# IDC_BNC_Adapter.net
KiCad netlist of a schematic drawn in Altium Designer
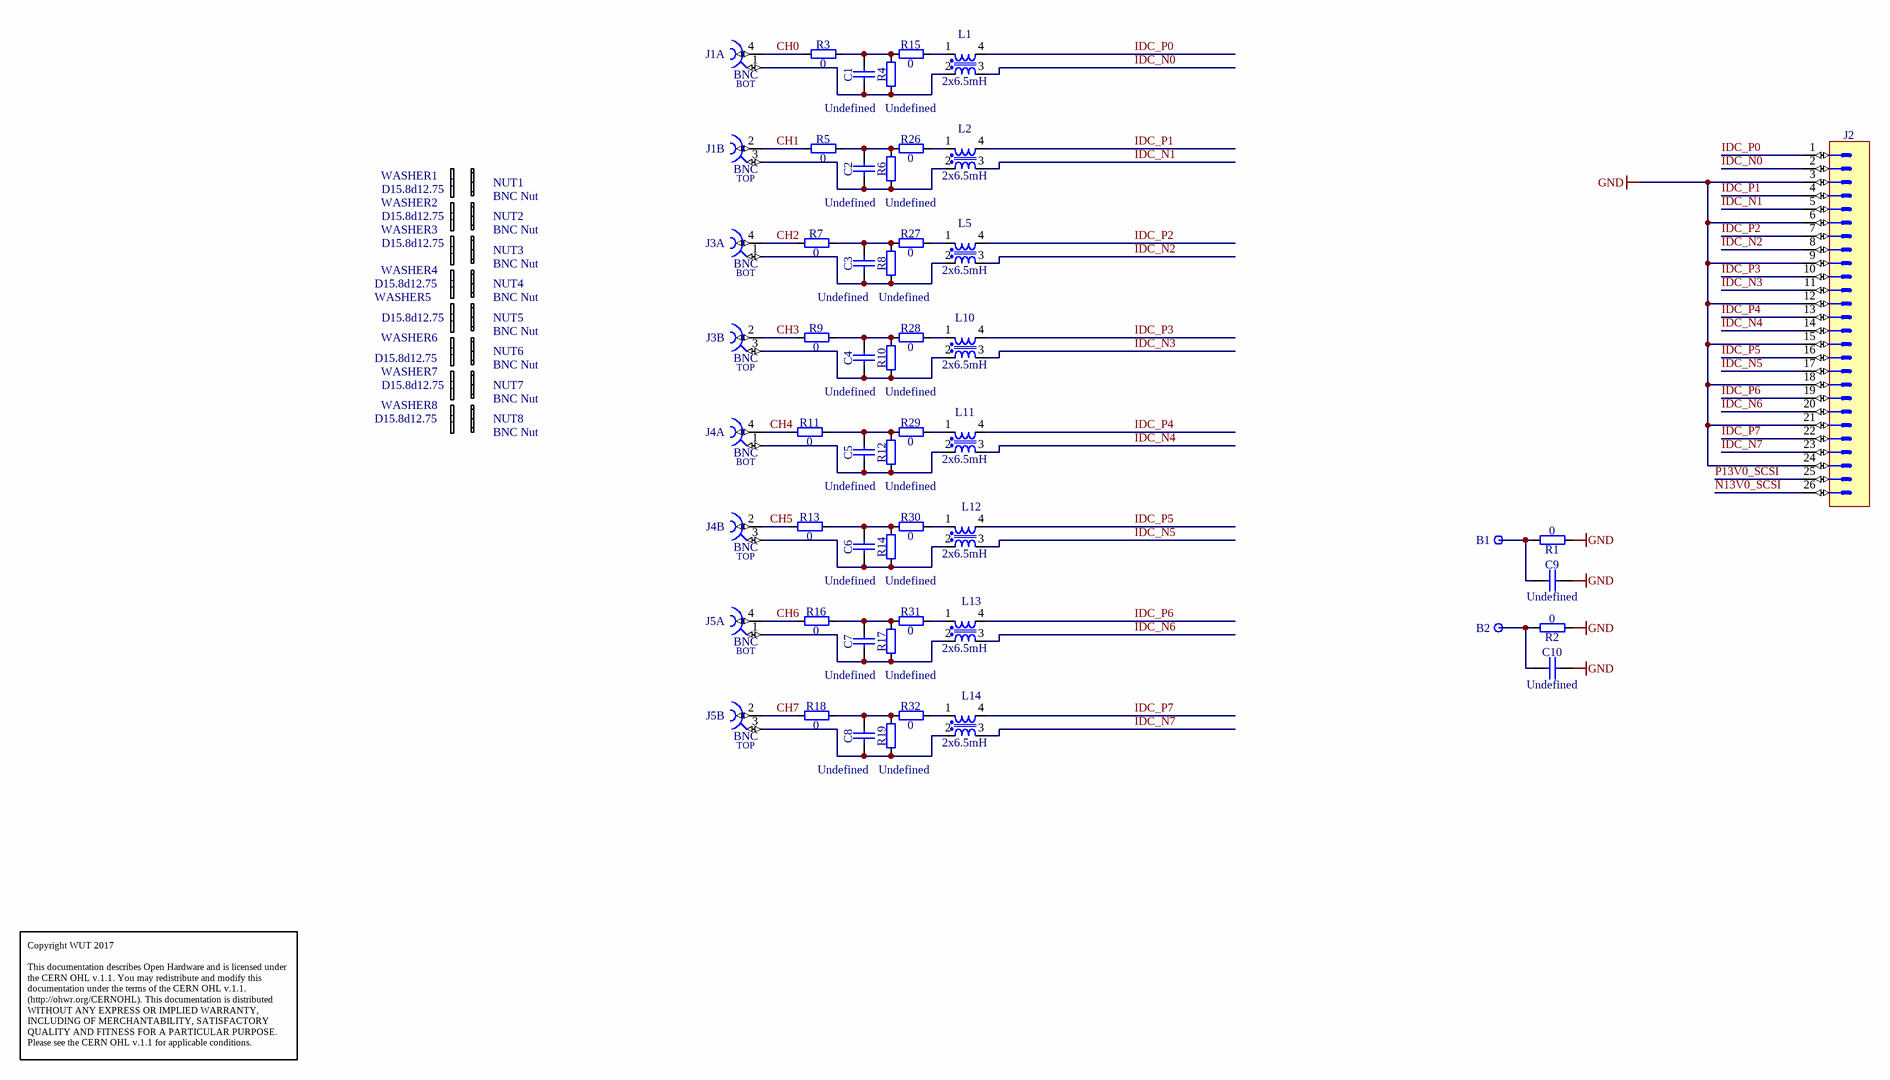
[diagram p0: IDC_BNC_Adapter.SchDoc]

(export (version "E")
  (design (tool "Eeschema 10.0.6"))
  (components
    (comp (ref "B1")
      (value "Plated Hole")
      (footprint "MTG270_500")
      (description "Single Terminal Socket")
      (fields (field (name "PART NUMBER") "PLATED_HOLE2.7_PAD5.0") (field (name "AUTHOR") "CERN DEM JMW"))
      (libsource (lib "Eletro-mechanical") (part "Single Terminal Socket"))
    )
    (comp (ref "B2")
      (value "Plated Hole")
      (footprint "MTG270_500")
      (description "Single Terminal Socket")
      (fields (field (name "PART NUMBER") "PLATED_HOLE2.7_PAD5.0") (field (name "AUTHOR") "CERN DEM JMW"))
      (libsource (lib "Eletro-mechanical") (part "Single Terminal Socket"))
    )
    (comp (ref "C1")
      (value "Undefined")
      (footprint "CAPC2012X135N")
      (description "Non-polarised capacitor")
      (fields (field (name "PART NUMBER") "CC0805_NO-VALUE") (field (name "AUTHOR") "CERN DEM JLC"))
      (libsource (lib "Capacitors") (part "Capacitor - non polarized"))
    )
    (comp (ref "C2")
      (value "Undefined")
      (footprint "CAPC2012X135N")
      (description "Non-polarised capacitor")
      (fields (field (name "PART NUMBER") "CC0805_NO-VALUE") (field (name "AUTHOR") "CERN DEM JLC"))
      (libsource (lib "Capacitors") (part "Capacitor - non polarized"))
    )
    (comp (ref "C3")
      (value "Undefined")
      (footprint "CAPC2012X135N")
      (description "Non-polarised capacitor")
      (fields (field (name "PART NUMBER") "CC0805_NO-VALUE") (field (name "AUTHOR") "CERN DEM JLC"))
      (libsource (lib "Capacitors") (part "Capacitor - non polarized"))
    )
    (comp (ref "C4")
      (value "Undefined")
      (footprint "CAPC2012X135N")
      (description "Non-polarised capacitor")
      (fields (field (name "PART NUMBER") "CC0805_NO-VALUE") (field (name "AUTHOR") "CERN DEM JLC"))
      (libsource (lib "Capacitors") (part "Capacitor - non polarized"))
    )
    (comp (ref "C5")
      (value "Undefined")
      (footprint "CAPC2012X135N")
      (description "Non-polarised capacitor")
      (fields (field (name "PART NUMBER") "CC0805_NO-VALUE") (field (name "AUTHOR") "CERN DEM JLC"))
      (libsource (lib "Capacitors") (part "Capacitor - non polarized"))
    )
    (comp (ref "C6")
      (value "Undefined")
      (footprint "CAPC2012X135N")
      (description "Non-polarised capacitor")
      (fields (field (name "PART NUMBER") "CC0805_NO-VALUE") (field (name "AUTHOR") "CERN DEM JLC"))
      (libsource (lib "Capacitors") (part "Capacitor - non polarized"))
    )
    (comp (ref "C7")
      (value "Undefined")
      (footprint "CAPC2012X135N")
      (description "Non-polarised capacitor")
      (fields (field (name "PART NUMBER") "CC0805_NO-VALUE") (field (name "AUTHOR") "CERN DEM JLC"))
      (libsource (lib "Capacitors") (part "Capacitor - non polarized"))
    )
    (comp (ref "C8")
      (value "Undefined")
      (footprint "CAPC2012X135N")
      (description "Non-polarised capacitor")
      (fields (field (name "PART NUMBER") "CC0805_NO-VALUE") (field (name "AUTHOR") "CERN DEM JLC"))
      (libsource (lib "Capacitors") (part "Capacitor - non polarized"))
    )
    (comp (ref "C9")
      (value "Undefined")
      (footprint "CAPC2012X135N")
      (description "Non-polarised capacitor")
      (fields (field (name "PART NUMBER") "CC0805_NO-VALUE") (field (name "AUTHOR") "CERN DEM JLC"))
      (libsource (lib "Capacitors") (part "Capacitor - non polarized"))
    )
    (comp (ref "C10")
      (value "Undefined")
      (footprint "CAPC2012X135N")
      (description "Non-polarised capacitor")
      (fields (field (name "PART NUMBER") "CC0805_NO-VALUE") (field (name "AUTHOR") "CERN DEM JLC"))
      (libsource (lib "Capacitors") (part "Capacitor - non polarized"))
    )
    (comp (ref "J1")
      (value "BNC")
      (footprint "RENHOTEC_RHT-610-0049")
      (description "Dual Right Angle 50 Ohm BNC Jack, White Valox Case")
      (fields
        (field (name "PART NUMBER") "RENHOTEC_RHT-610-0049")
        (field (name "MANUFACTURER") "RENHOTEC")
        (field (name "AUTHOR") "GK")
      )
      (libsource (lib "LIBRARY_SCH") (part "CON_BNC_DUAL"))
    )
    (comp (ref "J2")
      (value "Header 26")
      (footprint "3M_N2526-6003RB")
      (description "Connector 26 Male")
      (fields
        (field (name "PART NUMBER") "3M_N2526-6003RB")
        (field (name "MANUFACTURER") "3M")
        (field (name "AUTHOR") "CERN DEM JLC")
      )
      (libsource (lib "Connectors") (part "Connector 26 Male"))
    )
    (comp (ref "J3")
      (value "BNC")
      (footprint "RENHOTEC_RHT-610-0049")
      (description "Dual Right Angle 50 Ohm BNC Jack, White Valox Case")
      (fields
        (field (name "PART NUMBER") "RENHOTEC_RHT-610-0049")
        (field (name "MANUFACTURER") "RENHOTEC")
        (field (name "AUTHOR") "GK")
      )
      (libsource (lib "LIBRARY_SCH") (part "CON_BNC_DUAL"))
    )
    (comp (ref "J4")
      (value "BNC")
      (footprint "RENHOTEC_RHT-610-0049")
      (description "Dual Right Angle 50 Ohm BNC Jack, White Valox Case")
      (fields
        (field (name "PART NUMBER") "RENHOTEC_RHT-610-0049")
        (field (name "MANUFACTURER") "RENHOTEC")
        (field (name "AUTHOR") "GK")
      )
      (libsource (lib "LIBRARY_SCH") (part "CON_BNC_DUAL"))
    )
    (comp (ref "J5")
      (value "BNC")
      (footprint "RENHOTEC_RHT-610-0049")
      (description "Dual Right Angle 50 Ohm BNC Jack, White Valox Case")
      (fields
        (field (name "PART NUMBER") "RENHOTEC_RHT-610-0049")
        (field (name "MANUFACTURER") "RENHOTEC")
        (field (name "AUTHOR") "GK")
      )
      (libsource (lib "LIBRARY_SCH") (part "CON_BNC_DUAL"))
    )
    (comp (ref "L1")
      (value "2x6.5mH")
      (footprint "IND_WURTH_WE-SL2")
      (description "Inductor Common Mode")
      (fields
        (field (name "PART NUMBER") "IND_6.5MH_50%_WURTH_WE-SL2-744229")
        (field (name "POWER") "400mA")
        (field (name "AUTHOR") "CERN DEM JLC")
      )
      (libsource (lib "Inductors & Transformers") (part "Inductor Common Mode 1Dot-4 2Dot-3"))
    )
    (comp (ref "L2")
      (value "2x6.5mH")
      (footprint "IND_WURTH_WE-SL2")
      (description "Inductor Common Mode")
      (fields
        (field (name "PART NUMBER") "IND_6.5MH_50%_WURTH_WE-SL2-744229")
        (field (name "POWER") "400mA")
        (field (name "AUTHOR") "CERN DEM JLC")
      )
      (libsource (lib "Inductors & Transformers") (part "Inductor Common Mode 1Dot-4 2Dot-3"))
    )
    (comp (ref "L5")
      (value "2x6.5mH")
      (footprint "IND_WURTH_WE-SL2")
      (description "Inductor Common Mode")
      (fields
        (field (name "PART NUMBER") "IND_6.5MH_50%_WURTH_WE-SL2-744229")
        (field (name "POWER") "400mA")
        (field (name "AUTHOR") "CERN DEM JLC")
      )
      (libsource (lib "Inductors & Transformers") (part "Inductor Common Mode 1Dot-4 2Dot-3"))
    )
    (comp (ref "L10")
      (value "2x6.5mH")
      (footprint "IND_WURTH_WE-SL2")
      (description "Inductor Common Mode")
      (fields
        (field (name "PART NUMBER") "IND_6.5MH_50%_WURTH_WE-SL2-744229")
        (field (name "POWER") "400mA")
        (field (name "AUTHOR") "CERN DEM JLC")
      )
      (libsource (lib "Inductors & Transformers") (part "Inductor Common Mode 1Dot-4 2Dot-3"))
    )
    (comp (ref "L11")
      (value "2x6.5mH")
      (footprint "IND_WURTH_WE-SL2")
      (description "Inductor Common Mode")
      (fields
        (field (name "PART NUMBER") "IND_6.5MH_50%_WURTH_WE-SL2-744229")
        (field (name "POWER") "400mA")
        (field (name "AUTHOR") "CERN DEM JLC")
      )
      (libsource (lib "Inductors & Transformers") (part "Inductor Common Mode 1Dot-4 2Dot-3"))
    )
    (comp (ref "L12")
      (value "2x6.5mH")
      (footprint "IND_WURTH_WE-SL2")
      (description "Inductor Common Mode")
      (fields
        (field (name "PART NUMBER") "IND_6.5MH_50%_WURTH_WE-SL2-744229")
        (field (name "POWER") "400mA")
        (field (name "AUTHOR") "CERN DEM JLC")
      )
      (libsource (lib "Inductors & Transformers") (part "Inductor Common Mode 1Dot-4 2Dot-3"))
    )
    (comp (ref "L13")
      (value "2x6.5mH")
      (footprint "IND_WURTH_WE-SL2")
      (description "Inductor Common Mode")
      (fields
        (field (name "PART NUMBER") "IND_6.5MH_50%_WURTH_WE-SL2-744229")
        (field (name "POWER") "400mA")
        (field (name "AUTHOR") "CERN DEM JLC")
      )
      (libsource (lib "Inductors & Transformers") (part "Inductor Common Mode 1Dot-4 2Dot-3"))
    )
    (comp (ref "L14")
      (value "2x6.5mH")
      (footprint "IND_WURTH_WE-SL2")
      (description "Inductor Common Mode")
      (fields
        (field (name "PART NUMBER") "IND_6.5MH_50%_WURTH_WE-SL2-744229")
        (field (name "POWER") "400mA")
        (field (name "AUTHOR") "CERN DEM JLC")
      )
      (libsource (lib "Inductors & Transformers") (part "Inductor Common Mode 1Dot-4 2Dot-3"))
    )
    (comp (ref "NUT1")
      (value "BNC Nut")
      (footprint "TE_1-329631-2")
      (description "BNC nut")
      (fields
        (field (name "PART NUMBER") "TE_1-329631-2")
        (field (name "MANUFACTURER") "TE")
        (field (name "AUTHOR") "CERN DEM JLC")
      )
      (libsource (lib "LIBRARY_SCH") (part "MECH_BNC_NUT"))
    )
    (comp (ref "NUT2")
      (value "BNC Nut")
      (footprint "TE_1-329631-2")
      (description "BNC nut")
      (fields
        (field (name "PART NUMBER") "TE_1-329631-2")
        (field (name "MANUFACTURER") "TE")
        (field (name "AUTHOR") "CERN DEM JLC")
      )
      (libsource (lib "LIBRARY_SCH") (part "MECH_BNC_NUT"))
    )
    (comp (ref "NUT3")
      (value "BNC Nut")
      (footprint "TE_1-329631-2")
      (description "BNC nut")
      (fields
        (field (name "PART NUMBER") "TE_1-329631-2")
        (field (name "MANUFACTURER") "TE")
        (field (name "AUTHOR") "CERN DEM JLC")
      )
      (libsource (lib "LIBRARY_SCH") (part "MECH_BNC_NUT"))
    )
    (comp (ref "NUT4")
      (value "BNC Nut")
      (footprint "TE_1-329631-2")
      (description "BNC nut")
      (fields
        (field (name "PART NUMBER") "TE_1-329631-2")
        (field (name "MANUFACTURER") "TE")
        (field (name "AUTHOR") "CERN DEM JLC")
      )
      (libsource (lib "LIBRARY_SCH") (part "MECH_BNC_NUT"))
    )
    (comp (ref "NUT5")
      (value "BNC Nut")
      (footprint "TE_1-329631-2")
      (description "BNC nut")
      (fields
        (field (name "PART NUMBER") "TE_1-329631-2")
        (field (name "MANUFACTURER") "TE")
        (field (name "AUTHOR") "CERN DEM JLC")
      )
      (libsource (lib "LIBRARY_SCH") (part "MECH_BNC_NUT"))
    )
    (comp (ref "NUT6")
      (value "BNC Nut")
      (footprint "TE_1-329631-2")
      (description "BNC nut")
      (fields
        (field (name "PART NUMBER") "TE_1-329631-2")
        (field (name "MANUFACTURER") "TE")
        (field (name "AUTHOR") "CERN DEM JLC")
      )
      (libsource (lib "LIBRARY_SCH") (part "MECH_BNC_NUT"))
    )
    (comp (ref "NUT7")
      (value "BNC Nut")
      (footprint "TE_1-329631-2")
      (description "BNC nut")
      (fields
        (field (name "PART NUMBER") "TE_1-329631-2")
        (field (name "MANUFACTURER") "TE")
        (field (name "AUTHOR") "CERN DEM JLC")
      )
      (libsource (lib "LIBRARY_SCH") (part "MECH_BNC_NUT"))
    )
    (comp (ref "NUT8")
      (value "BNC Nut")
      (footprint "TE_1-329631-2")
      (description "BNC nut")
      (fields
        (field (name "PART NUMBER") "TE_1-329631-2")
        (field (name "MANUFACTURER") "TE")
        (field (name "AUTHOR") "CERN DEM JLC")
      )
      (libsource (lib "LIBRARY_SCH") (part "MECH_BNC_NUT"))
    )
    (comp (ref "R1")
      (value "0")
      (footprint "RESC1608X55N")
      (description "Resistor")
      (fields
        (field (name "PART NUMBER") "R0603_0R_JUMPER")
        (field (name "MANUFACTURER") "GENERIC")
        (field (name "AUTHOR") "CERN DEM JLC")
      )
      (libsource (lib "Resistors") (part "Resistor"))
    )
    (comp (ref "R2")
      (value "0")
      (footprint "RESC1608X55N")
      (description "Resistor")
      (fields
        (field (name "PART NUMBER") "R0603_0R_JUMPER")
        (field (name "MANUFACTURER") "GENERIC")
        (field (name "AUTHOR") "CERN DEM JLC")
      )
      (libsource (lib "Resistors") (part "Resistor"))
    )
    (comp (ref "R3")
      (value "0")
      (footprint "RESC1608X55N")
      (description "Resistor")
      (fields
        (field (name "PART NUMBER") "R0603_0R_JUMPER")
        (field (name "MANUFACTURER") "GENERIC")
        (field (name "AUTHOR") "CERN DEM JLC")
      )
      (libsource (lib "Resistors") (part "Resistor"))
    )
    (comp (ref "R4")
      (value "Undefined")
      (footprint "RESC1608X55N")
      (description "Resistor")
      (fields (field (name "PART NUMBER") "R0603_NO-VALUE") (field (name "AUTHOR") "CERN DEM JLC"))
      (libsource (lib "Resistors") (part "Resistor"))
    )
    (comp (ref "R5")
      (value "0")
      (footprint "RESC1608X55N")
      (description "Resistor")
      (fields
        (field (name "PART NUMBER") "R0603_0R_JUMPER")
        (field (name "MANUFACTURER") "GENERIC")
        (field (name "AUTHOR") "CERN DEM JLC")
      )
      (libsource (lib "Resistors") (part "Resistor"))
    )
    (comp (ref "R6")
      (value "Undefined")
      (footprint "RESC1608X55N")
      (description "Resistor")
      (fields (field (name "PART NUMBER") "R0603_NO-VALUE") (field (name "AUTHOR") "CERN DEM JLC"))
      (libsource (lib "Resistors") (part "Resistor"))
    )
    (comp (ref "R7")
      (value "0")
      (footprint "RESC1608X55N")
      (description "Resistor")
      (fields
        (field (name "PART NUMBER") "R0603_0R_JUMPER")
        (field (name "MANUFACTURER") "GENERIC")
        (field (name "AUTHOR") "CERN DEM JLC")
      )
      (libsource (lib "Resistors") (part "Resistor"))
    )
    (comp (ref "R8")
      (value "Undefined")
      (footprint "RESC1608X55N")
      (description "Resistor")
      (fields (field (name "PART NUMBER") "R0603_NO-VALUE") (field (name "AUTHOR") "CERN DEM JLC"))
      (libsource (lib "Resistors") (part "Resistor"))
    )
    (comp (ref "R9")
      (value "0")
      (footprint "RESC1608X55N")
      (description "Resistor")
      (fields
        (field (name "PART NUMBER") "R0603_0R_JUMPER")
        (field (name "MANUFACTURER") "GENERIC")
        (field (name "AUTHOR") "CERN DEM JLC")
      )
      (libsource (lib "Resistors") (part "Resistor"))
    )
    (comp (ref "R10")
      (value "Undefined")
      (footprint "RESC1608X55N")
      (description "Resistor")
      (fields (field (name "PART NUMBER") "R0603_NO-VALUE") (field (name "AUTHOR") "CERN DEM JLC"))
      (libsource (lib "Resistors") (part "Resistor"))
    )
    (comp (ref "R11")
      (value "0")
      (footprint "RESC1608X55N")
      (description "Resistor")
      (fields
        (field (name "PART NUMBER") "R0603_0R_JUMPER")
        (field (name "MANUFACTURER") "GENERIC")
        (field (name "AUTHOR") "CERN DEM JLC")
      )
      (libsource (lib "Resistors") (part "Resistor"))
    )
    (comp (ref "R12")
      (value "Undefined")
      (footprint "RESC1608X55N")
      (description "Resistor")
      (fields (field (name "PART NUMBER") "R0603_NO-VALUE") (field (name "AUTHOR") "CERN DEM JLC"))
      (libsource (lib "Resistors") (part "Resistor"))
    )
    (comp (ref "R13")
      (value "0")
      (footprint "RESC1608X55N")
      (description "Resistor")
      (fields
        (field (name "PART NUMBER") "R0603_0R_JUMPER")
        (field (name "MANUFACTURER") "GENERIC")
        (field (name "AUTHOR") "CERN DEM JLC")
      )
      (libsource (lib "Resistors") (part "Resistor"))
    )
    (comp (ref "R14")
      (value "Undefined")
      (footprint "RESC1608X55N")
      (description "Resistor")
      (fields (field (name "PART NUMBER") "R0603_NO-VALUE") (field (name "AUTHOR") "CERN DEM JLC"))
      (libsource (lib "Resistors") (part "Resistor"))
    )
    (comp (ref "R15")
      (value "0")
      (footprint "RESC1608X55N")
      (description "Resistor")
      (fields
        (field (name "PART NUMBER") "R0603_0R_JUMPER")
        (field (name "MANUFACTURER") "GENERIC")
        (field (name "AUTHOR") "CERN DEM JLC")
      )
      (libsource (lib "Resistors") (part "Resistor"))
    )
    (comp (ref "R16")
      (value "0")
      (footprint "RESC1608X55N")
      (description "Resistor")
      (fields
        (field (name "PART NUMBER") "R0603_0R_JUMPER")
        (field (name "MANUFACTURER") "GENERIC")
        (field (name "AUTHOR") "CERN DEM JLC")
      )
      (libsource (lib "Resistors") (part "Resistor"))
    )
    (comp (ref "R17")
      (value "Undefined")
      (footprint "RESC1608X55N")
      (description "Resistor")
      (fields (field (name "PART NUMBER") "R0603_NO-VALUE") (field (name "AUTHOR") "CERN DEM JLC"))
      (libsource (lib "Resistors") (part "Resistor"))
    )
    (comp (ref "R18")
      (value "0")
      (footprint "RESC1608X55N")
      (description "Resistor")
      (fields
        (field (name "PART NUMBER") "R0603_0R_JUMPER")
        (field (name "MANUFACTURER") "GENERIC")
        (field (name "AUTHOR") "CERN DEM JLC")
      )
      (libsource (lib "Resistors") (part "Resistor"))
    )
    (comp (ref "R19")
      (value "Undefined")
      (footprint "RESC1608X55N")
      (description "Resistor")
      (fields (field (name "PART NUMBER") "R0603_NO-VALUE") (field (name "AUTHOR") "CERN DEM JLC"))
      (libsource (lib "Resistors") (part "Resistor"))
    )
    (comp (ref "R26")
      (value "0")
      (footprint "RESC1608X55N")
      (description "Resistor")
      (fields
        (field (name "PART NUMBER") "R0603_0R_JUMPER")
        (field (name "MANUFACTURER") "GENERIC")
        (field (name "AUTHOR") "CERN DEM JLC")
      )
      (libsource (lib "Resistors") (part "Resistor"))
    )
    (comp (ref "R27")
      (value "0")
      (footprint "RESC1608X55N")
      (description "Resistor")
      (fields
        (field (name "PART NUMBER") "R0603_0R_JUMPER")
        (field (name "MANUFACTURER") "GENERIC")
        (field (name "AUTHOR") "CERN DEM JLC")
      )
      (libsource (lib "Resistors") (part "Resistor"))
    )
    (comp (ref "R28")
      (value "0")
      (footprint "RESC1608X55N")
      (description "Resistor")
      (fields
        (field (name "PART NUMBER") "R0603_0R_JUMPER")
        (field (name "MANUFACTURER") "GENERIC")
        (field (name "AUTHOR") "CERN DEM JLC")
      )
      (libsource (lib "Resistors") (part "Resistor"))
    )
    (comp (ref "R29")
      (value "0")
      (footprint "RESC1608X55N")
      (description "Resistor")
      (fields
        (field (name "PART NUMBER") "R0603_0R_JUMPER")
        (field (name "MANUFACTURER") "GENERIC")
        (field (name "AUTHOR") "CERN DEM JLC")
      )
      (libsource (lib "Resistors") (part "Resistor"))
    )
    (comp (ref "R30")
      (value "0")
      (footprint "RESC1608X55N")
      (description "Resistor")
      (fields
        (field (name "PART NUMBER") "R0603_0R_JUMPER")
        (field (name "MANUFACTURER") "GENERIC")
        (field (name "AUTHOR") "CERN DEM JLC")
      )
      (libsource (lib "Resistors") (part "Resistor"))
    )
    (comp (ref "R31")
      (value "0")
      (footprint "RESC1608X55N")
      (description "Resistor")
      (fields
        (field (name "PART NUMBER") "R0603_0R_JUMPER")
        (field (name "MANUFACTURER") "GENERIC")
        (field (name "AUTHOR") "CERN DEM JLC")
      )
      (libsource (lib "Resistors") (part "Resistor"))
    )
    (comp (ref "R32")
      (value "0")
      (footprint "RESC1608X55N")
      (description "Resistor")
      (fields
        (field (name "PART NUMBER") "R0603_0R_JUMPER")
        (field (name "MANUFACTURER") "GENERIC")
        (field (name "AUTHOR") "CERN DEM JLC")
      )
      (libsource (lib "Resistors") (part "Resistor"))
    )
    (comp (ref "WASHER1")
      (value "D15.8d12.75")
      (footprint "TE_1-1634817-0")
      (description "BNC Washer")
      (fields
        (field (name "PART NUMBER") "TE_1-1634817-0")
        (field (name "MANUFACTURER") "TE")
        (field (name "AUTHOR") "GK")
      )
      (libsource (lib "LIBRARY_SCH") (part "MECH_BNC_WASHER"))
    )
    (comp (ref "WASHER2")
      (value "D15.8d12.75")
      (footprint "TE_1-1634817-0")
      (description "BNC Washer")
      (fields
        (field (name "PART NUMBER") "TE_1-1634817-0")
        (field (name "MANUFACTURER") "TE")
        (field (name "AUTHOR") "GK")
      )
      (libsource (lib "LIBRARY_SCH") (part "MECH_BNC_WASHER"))
    )
    (comp (ref "WASHER3")
      (value "D15.8d12.75")
      (footprint "TE_1-1634817-0")
      (description "BNC Washer")
      (fields
        (field (name "PART NUMBER") "TE_1-1634817-0")
        (field (name "MANUFACTURER") "TE")
        (field (name "AUTHOR") "GK")
      )
      (libsource (lib "LIBRARY_SCH") (part "MECH_BNC_WASHER"))
    )
    (comp (ref "WASHER4")
      (value "D15.8d12.75")
      (footprint "TE_1-1634817-0")
      (description "BNC Washer")
      (fields
        (field (name "PART NUMBER") "TE_1-1634817-0")
        (field (name "MANUFACTURER") "TE")
        (field (name "AUTHOR") "GK")
      )
      (libsource (lib "LIBRARY_SCH") (part "MECH_BNC_WASHER"))
    )
    (comp (ref "WASHER5")
      (value "D15.8d12.75")
      (footprint "TE_1-1634817-0")
      (description "BNC Washer")
      (fields
        (field (name "PART NUMBER") "TE_1-1634817-0")
        (field (name "MANUFACTURER") "TE")
        (field (name "AUTHOR") "GK")
      )
      (libsource (lib "LIBRARY_SCH") (part "MECH_BNC_WASHER"))
    )
    (comp (ref "WASHER6")
      (value "D15.8d12.75")
      (footprint "TE_1-1634817-0")
      (description "BNC Washer")
      (fields
        (field (name "PART NUMBER") "TE_1-1634817-0")
        (field (name "MANUFACTURER") "TE")
        (field (name "AUTHOR") "GK")
      )
      (libsource (lib "LIBRARY_SCH") (part "MECH_BNC_WASHER"))
    )
    (comp (ref "WASHER7")
      (value "D15.8d12.75")
      (footprint "TE_1-1634817-0")
      (description "BNC Washer")
      (fields
        (field (name "PART NUMBER") "TE_1-1634817-0")
        (field (name "MANUFACTURER") "TE")
        (field (name "AUTHOR") "GK")
      )
      (libsource (lib "LIBRARY_SCH") (part "MECH_BNC_WASHER"))
    )
    (comp (ref "WASHER8")
      (value "D15.8d12.75")
      (footprint "TE_1-1634817-0")
      (description "BNC Washer")
      (fields
        (field (name "PART NUMBER") "TE_1-1634817-0")
        (field (name "MANUFACTURER") "TE")
        (field (name "AUTHOR") "GK")
      )
      (libsource (lib "LIBRARY_SCH") (part "MECH_BNC_WASHER"))
    )
  )
  (nets
    (net (code "1") (name "/CH0") (class "Default")
      (node (ref "J1") (pin "4") (pinfunction "4_4") (pintype "bidirectional"))
      (node (ref "R3") (pin "1") (pinfunction "1_1") (pintype "passive"))
    )
    (net (code "2") (name "/CH1") (class "Default")
      (node (ref "J1") (pin "2") (pinfunction "2_2") (pintype "bidirectional"))
      (node (ref "R5") (pin "1") (pinfunction "1_1") (pintype "passive"))
    )
    (net (code "3") (name "/CH2") (class "Default")
      (node (ref "J3") (pin "4") (pinfunction "4_4") (pintype "bidirectional"))
      (node (ref "R7") (pin "1") (pinfunction "1_1") (pintype "passive"))
    )
    (net (code "4") (name "/CH3") (class "Default")
      (node (ref "J3") (pin "2") (pinfunction "2_2") (pintype "bidirectional"))
      (node (ref "R9") (pin "1") (pinfunction "1_1") (pintype "passive"))
    )
    (net (code "5") (name "/CH4") (class "Default")
      (node (ref "J4") (pin "4") (pinfunction "4_4") (pintype "bidirectional"))
      (node (ref "R11") (pin "1") (pinfunction "1_1") (pintype "passive"))
    )
    (net (code "6") (name "/CH5") (class "Default")
      (node (ref "J4") (pin "2") (pinfunction "2_2") (pintype "bidirectional"))
      (node (ref "R13") (pin "1") (pinfunction "1_1") (pintype "passive"))
    )
    (net (code "7") (name "/CH6") (class "Default")
      (node (ref "J5") (pin "4") (pinfunction "4_4") (pintype "bidirectional"))
      (node (ref "R16") (pin "1") (pinfunction "1_1") (pintype "passive"))
    )
    (net (code "8") (name "/CH7") (class "Default")
      (node (ref "J5") (pin "2") (pinfunction "2_2") (pintype "bidirectional"))
      (node (ref "R18") (pin "1") (pinfunction "1_1") (pintype "passive"))
    )
    (net (code "9") (name "/IDC_N0") (class "Default")
      (node (ref "J2") (pin "2") (pinfunction "2_2") (pintype "bidirectional"))
      (node (ref "L1") (pin "3") (pinfunction "3_3") (pintype "passive"))
    )
    (net (code "10") (name "/IDC_N1") (class "Default")
      (node (ref "J2") (pin "5") (pinfunction "5_5") (pintype "bidirectional"))
      (node (ref "L2") (pin "3") (pinfunction "3_3") (pintype "passive"))
    )
    (net (code "11") (name "/IDC_N2") (class "Default")
      (node (ref "J2") (pin "8") (pinfunction "8_8") (pintype "bidirectional"))
      (node (ref "L5") (pin "3") (pinfunction "3_3") (pintype "passive"))
    )
    (net (code "12") (name "/IDC_N3") (class "Default")
      (node (ref "J2") (pin "11") (pinfunction "11_11") (pintype "bidirectional"))
      (node (ref "L10") (pin "3") (pinfunction "3_3") (pintype "passive"))
    )
    (net (code "13") (name "/IDC_N4") (class "Default")
      (node (ref "J2") (pin "14") (pinfunction "14_14") (pintype "bidirectional"))
      (node (ref "L11") (pin "3") (pinfunction "3_3") (pintype "passive"))
    )
    (net (code "14") (name "/IDC_N5") (class "Default")
      (node (ref "J2") (pin "17") (pinfunction "17_17") (pintype "bidirectional"))
      (node (ref "L12") (pin "3") (pinfunction "3_3") (pintype "passive"))
    )
    (net (code "15") (name "/IDC_N6") (class "Default")
      (node (ref "J2") (pin "20") (pinfunction "20_20") (pintype "bidirectional"))
      (node (ref "L13") (pin "3") (pinfunction "3_3") (pintype "passive"))
    )
    (net (code "16") (name "/IDC_N7") (class "Default")
      (node (ref "J2") (pin "23") (pinfunction "23_23") (pintype "bidirectional"))
      (node (ref "L14") (pin "3") (pinfunction "3_3") (pintype "passive"))
    )
    (net (code "17") (name "/IDC_P0") (class "Default")
      (node (ref "J2") (pin "1") (pinfunction "1_1") (pintype "bidirectional"))
      (node (ref "L1") (pin "4") (pinfunction "4_4") (pintype "passive"))
    )
    (net (code "18") (name "/IDC_P1") (class "Default")
      (node (ref "J2") (pin "4") (pinfunction "4_4") (pintype "bidirectional"))
      (node (ref "L2") (pin "4") (pinfunction "4_4") (pintype "passive"))
    )
    (net (code "19") (name "/IDC_P2") (class "Default")
      (node (ref "J2") (pin "7") (pinfunction "7_7") (pintype "bidirectional"))
      (node (ref "L5") (pin "4") (pinfunction "4_4") (pintype "passive"))
    )
    (net (code "20") (name "/IDC_P3") (class "Default")
      (node (ref "J2") (pin "10") (pinfunction "10_10") (pintype "bidirectional"))
      (node (ref "L10") (pin "4") (pinfunction "4_4") (pintype "passive"))
    )
    (net (code "21") (name "/IDC_P4") (class "Default")
      (node (ref "J2") (pin "13") (pinfunction "13_13") (pintype "bidirectional"))
      (node (ref "L11") (pin "4") (pinfunction "4_4") (pintype "passive"))
    )
    (net (code "22") (name "/IDC_P5") (class "Default")
      (node (ref "J2") (pin "16") (pinfunction "16_16") (pintype "bidirectional"))
      (node (ref "L12") (pin "4") (pinfunction "4_4") (pintype "passive"))
    )
    (net (code "23") (name "/IDC_P6") (class "Default")
      (node (ref "J2") (pin "19") (pinfunction "19_19") (pintype "bidirectional"))
      (node (ref "L13") (pin "4") (pinfunction "4_4") (pintype "passive"))
    )
    (net (code "24") (name "/IDC_P7") (class "Default")
      (node (ref "J2") (pin "22") (pinfunction "22_22") (pintype "bidirectional"))
      (node (ref "L14") (pin "4") (pinfunction "4_4") (pintype "passive"))
    )
    (net (code "25") (name "/N13V0_SCSI") (class "Default")
      (node (ref "J2") (pin "26") (pinfunction "26_26") (pintype "bidirectional"))
    )
    (net (code "26") (name "/P13V0_SCSI") (class "Default")
      (node (ref "J2") (pin "25") (pinfunction "25_25") (pintype "bidirectional"))
    )
    (net (code "27") (name "GND") (class "Default")
      (node (ref "C10") (pin "2") (pinfunction "2_2") (pintype "passive"))
      (node (ref "C9") (pin "2") (pinfunction "2_2") (pintype "passive"))
      (node (ref "J2") (pin "12") (pinfunction "12_12") (pintype "bidirectional"))
      (node (ref "J2") (pin "15") (pinfunction "15_15") (pintype "bidirectional"))
      (node (ref "J2") (pin "18") (pinfunction "18_18") (pintype "bidirectional"))
      (node (ref "J2") (pin "21") (pinfunction "21_21") (pintype "bidirectional"))
      (node (ref "J2") (pin "24") (pinfunction "24_24") (pintype "bidirectional"))
      (node (ref "J2") (pin "3") (pinfunction "3_3") (pintype "bidirectional"))
      (node (ref "J2") (pin "6") (pinfunction "6_6") (pintype "bidirectional"))
      (node (ref "J2") (pin "9") (pinfunction "9_9") (pintype "bidirectional"))
      (node (ref "R1") (pin "1") (pinfunction "1_1") (pintype "passive"))
      (node (ref "R2") (pin "1") (pinfunction "1_1") (pintype "passive"))
    )
    (net (code "28") (name "Net-(B1-Pad1)") (class "Default")
      (node (ref "B1") (pin "1") (pinfunction "1_1") (pintype "bidirectional"))
      (node (ref "C9") (pin "1") (pinfunction "1_1") (pintype "passive"))
      (node (ref "R1") (pin "2") (pinfunction "2_2") (pintype "passive"))
    )
    (net (code "29") (name "Net-(B2-Pad1)") (class "Default")
      (node (ref "B2") (pin "1") (pinfunction "1_1") (pintype "bidirectional"))
      (node (ref "C10") (pin "1") (pinfunction "1_1") (pintype "passive"))
      (node (ref "R2") (pin "2") (pinfunction "2_2") (pintype "passive"))
    )
    (net (code "30") (name "Net-(C1-Pad1)") (class "Default")
      (node (ref "C1") (pin "1") (pinfunction "1_1") (pintype "passive"))
      (node (ref "J1") (pin "1") (pinfunction "1_1") (pintype "bidirectional"))
      (node (ref "L1") (pin "2") (pinfunction "2_2") (pintype "passive"))
      (node (ref "R4") (pin "1") (pinfunction "1_1") (pintype "passive"))
    )
    (net (code "31") (name "Net-(C1-Pad2)") (class "Default")
      (node (ref "C1") (pin "2") (pinfunction "2_2") (pintype "passive"))
      (node (ref "R15") (pin "1") (pinfunction "1_1") (pintype "passive"))
      (node (ref "R3") (pin "2") (pinfunction "2_2") (pintype "passive"))
      (node (ref "R4") (pin "2") (pinfunction "2_2") (pintype "passive"))
    )
    (net (code "32") (name "Net-(C2-Pad1)") (class "Default")
      (node (ref "C2") (pin "1") (pinfunction "1_1") (pintype "passive"))
      (node (ref "J1") (pin "3") (pinfunction "3_3") (pintype "bidirectional"))
      (node (ref "L2") (pin "2") (pinfunction "2_2") (pintype "passive"))
      (node (ref "R6") (pin "1") (pinfunction "1_1") (pintype "passive"))
    )
    (net (code "33") (name "Net-(C2-Pad2)") (class "Default")
      (node (ref "C2") (pin "2") (pinfunction "2_2") (pintype "passive"))
      (node (ref "R26") (pin "1") (pinfunction "1_1") (pintype "passive"))
      (node (ref "R5") (pin "2") (pinfunction "2_2") (pintype "passive"))
      (node (ref "R6") (pin "2") (pinfunction "2_2") (pintype "passive"))
    )
    (net (code "34") (name "Net-(C3-Pad1)") (class "Default")
      (node (ref "C3") (pin "1") (pinfunction "1_1") (pintype "passive"))
      (node (ref "J3") (pin "1") (pinfunction "1_1") (pintype "bidirectional"))
      (node (ref "L5") (pin "2") (pinfunction "2_2") (pintype "passive"))
      (node (ref "R8") (pin "1") (pinfunction "1_1") (pintype "passive"))
    )
    (net (code "35") (name "Net-(C3-Pad2)") (class "Default")
      (node (ref "C3") (pin "2") (pinfunction "2_2") (pintype "passive"))
      (node (ref "R27") (pin "1") (pinfunction "1_1") (pintype "passive"))
      (node (ref "R7") (pin "2") (pinfunction "2_2") (pintype "passive"))
      (node (ref "R8") (pin "2") (pinfunction "2_2") (pintype "passive"))
    )
    (net (code "36") (name "Net-(C4-Pad1)") (class "Default")
      (node (ref "C4") (pin "1") (pinfunction "1_1") (pintype "passive"))
      (node (ref "J3") (pin "3") (pinfunction "3_3") (pintype "bidirectional"))
      (node (ref "L10") (pin "2") (pinfunction "2_2") (pintype "passive"))
      (node (ref "R10") (pin "1") (pinfunction "1_1") (pintype "passive"))
    )
    (net (code "37") (name "Net-(C4-Pad2)") (class "Default")
      (node (ref "C4") (pin "2") (pinfunction "2_2") (pintype "passive"))
      (node (ref "R10") (pin "2") (pinfunction "2_2") (pintype "passive"))
      (node (ref "R28") (pin "1") (pinfunction "1_1") (pintype "passive"))
      (node (ref "R9") (pin "2") (pinfunction "2_2") (pintype "passive"))
    )
    (net (code "38") (name "Net-(C5-Pad1)") (class "Default")
      (node (ref "C5") (pin "1") (pinfunction "1_1") (pintype "passive"))
      (node (ref "J4") (pin "1") (pinfunction "1_1") (pintype "bidirectional"))
      (node (ref "L11") (pin "2") (pinfunction "2_2") (pintype "passive"))
      (node (ref "R12") (pin "1") (pinfunction "1_1") (pintype "passive"))
    )
    (net (code "39") (name "Net-(C5-Pad2)") (class "Default")
      (node (ref "C5") (pin "2") (pinfunction "2_2") (pintype "passive"))
      (node (ref "R11") (pin "2") (pinfunction "2_2") (pintype "passive"))
      (node (ref "R12") (pin "2") (pinfunction "2_2") (pintype "passive"))
      (node (ref "R29") (pin "1") (pinfunction "1_1") (pintype "passive"))
    )
    (net (code "40") (name "Net-(C6-Pad1)") (class "Default")
      (node (ref "C6") (pin "1") (pinfunction "1_1") (pintype "passive"))
      (node (ref "J4") (pin "3") (pinfunction "3_3") (pintype "bidirectional"))
      (node (ref "L12") (pin "2") (pinfunction "2_2") (pintype "passive"))
      (node (ref "R14") (pin "1") (pinfunction "1_1") (pintype "passive"))
    )
    (net (code "41") (name "Net-(C6-Pad2)") (class "Default")
      (node (ref "C6") (pin "2") (pinfunction "2_2") (pintype "passive"))
      (node (ref "R13") (pin "2") (pinfunction "2_2") (pintype "passive"))
      (node (ref "R14") (pin "2") (pinfunction "2_2") (pintype "passive"))
      (node (ref "R30") (pin "1") (pinfunction "1_1") (pintype "passive"))
    )
    (net (code "42") (name "Net-(C7-Pad1)") (class "Default")
      (node (ref "C7") (pin "1") (pinfunction "1_1") (pintype "passive"))
      (node (ref "J5") (pin "1") (pinfunction "1_1") (pintype "bidirectional"))
      (node (ref "L13") (pin "2") (pinfunction "2_2") (pintype "passive"))
      (node (ref "R17") (pin "1") (pinfunction "1_1") (pintype "passive"))
    )
    (net (code "43") (name "Net-(C7-Pad2)") (class "Default")
      (node (ref "C7") (pin "2") (pinfunction "2_2") (pintype "passive"))
      (node (ref "R16") (pin "2") (pinfunction "2_2") (pintype "passive"))
      (node (ref "R17") (pin "2") (pinfunction "2_2") (pintype "passive"))
      (node (ref "R31") (pin "1") (pinfunction "1_1") (pintype "passive"))
    )
    (net (code "44") (name "Net-(C8-Pad1)") (class "Default")
      (node (ref "C8") (pin "1") (pinfunction "1_1") (pintype "passive"))
      (node (ref "J5") (pin "3") (pinfunction "3_3") (pintype "bidirectional"))
      (node (ref "L14") (pin "2") (pinfunction "2_2") (pintype "passive"))
      (node (ref "R19") (pin "1") (pinfunction "1_1") (pintype "passive"))
    )
    (net (code "45") (name "Net-(C8-Pad2)") (class "Default")
      (node (ref "C8") (pin "2") (pinfunction "2_2") (pintype "passive"))
      (node (ref "R18") (pin "2") (pinfunction "2_2") (pintype "passive"))
      (node (ref "R19") (pin "2") (pinfunction "2_2") (pintype "passive"))
      (node (ref "R32") (pin "1") (pinfunction "1_1") (pintype "passive"))
    )
    (net (code "46") (name "Net-(L1-Pad1)") (class "Default")
      (node (ref "L1") (pin "1") (pinfunction "1_1") (pintype "passive"))
      (node (ref "R15") (pin "2") (pinfunction "2_2") (pintype "passive"))
    )
    (net (code "47") (name "Net-(L2-Pad1)") (class "Default")
      (node (ref "L2") (pin "1") (pinfunction "1_1") (pintype "passive"))
      (node (ref "R26") (pin "2") (pinfunction "2_2") (pintype "passive"))
    )
    (net (code "48") (name "Net-(L5-Pad1)") (class "Default")
      (node (ref "L5") (pin "1") (pinfunction "1_1") (pintype "passive"))
      (node (ref "R27") (pin "2") (pinfunction "2_2") (pintype "passive"))
    )
    (net (code "49") (name "Net-(L10-Pad1)") (class "Default")
      (node (ref "L10") (pin "1") (pinfunction "1_1") (pintype "passive"))
      (node (ref "R28") (pin "2") (pinfunction "2_2") (pintype "passive"))
    )
    (net (code "50") (name "Net-(L11-Pad1)") (class "Default")
      (node (ref "L11") (pin "1") (pinfunction "1_1") (pintype "passive"))
      (node (ref "R29") (pin "2") (pinfunction "2_2") (pintype "passive"))
    )
    (net (code "51") (name "Net-(L12-Pad1)") (class "Default")
      (node (ref "L12") (pin "1") (pinfunction "1_1") (pintype "passive"))
      (node (ref "R30") (pin "2") (pinfunction "2_2") (pintype "passive"))
    )
    (net (code "52") (name "Net-(L13-Pad1)") (class "Default")
      (node (ref "L13") (pin "1") (pinfunction "1_1") (pintype "passive"))
      (node (ref "R31") (pin "2") (pinfunction "2_2") (pintype "passive"))
    )
    (net (code "53") (name "Net-(L14-Pad1)") (class "Default")
      (node (ref "L14") (pin "1") (pinfunction "1_1") (pintype "passive"))
      (node (ref "R32") (pin "2") (pinfunction "2_2") (pintype "passive"))
    )
  )
)
